# Amulet_watch_kite_d_companion.net
KiCad netlist of a schematic drawn in EAGLE
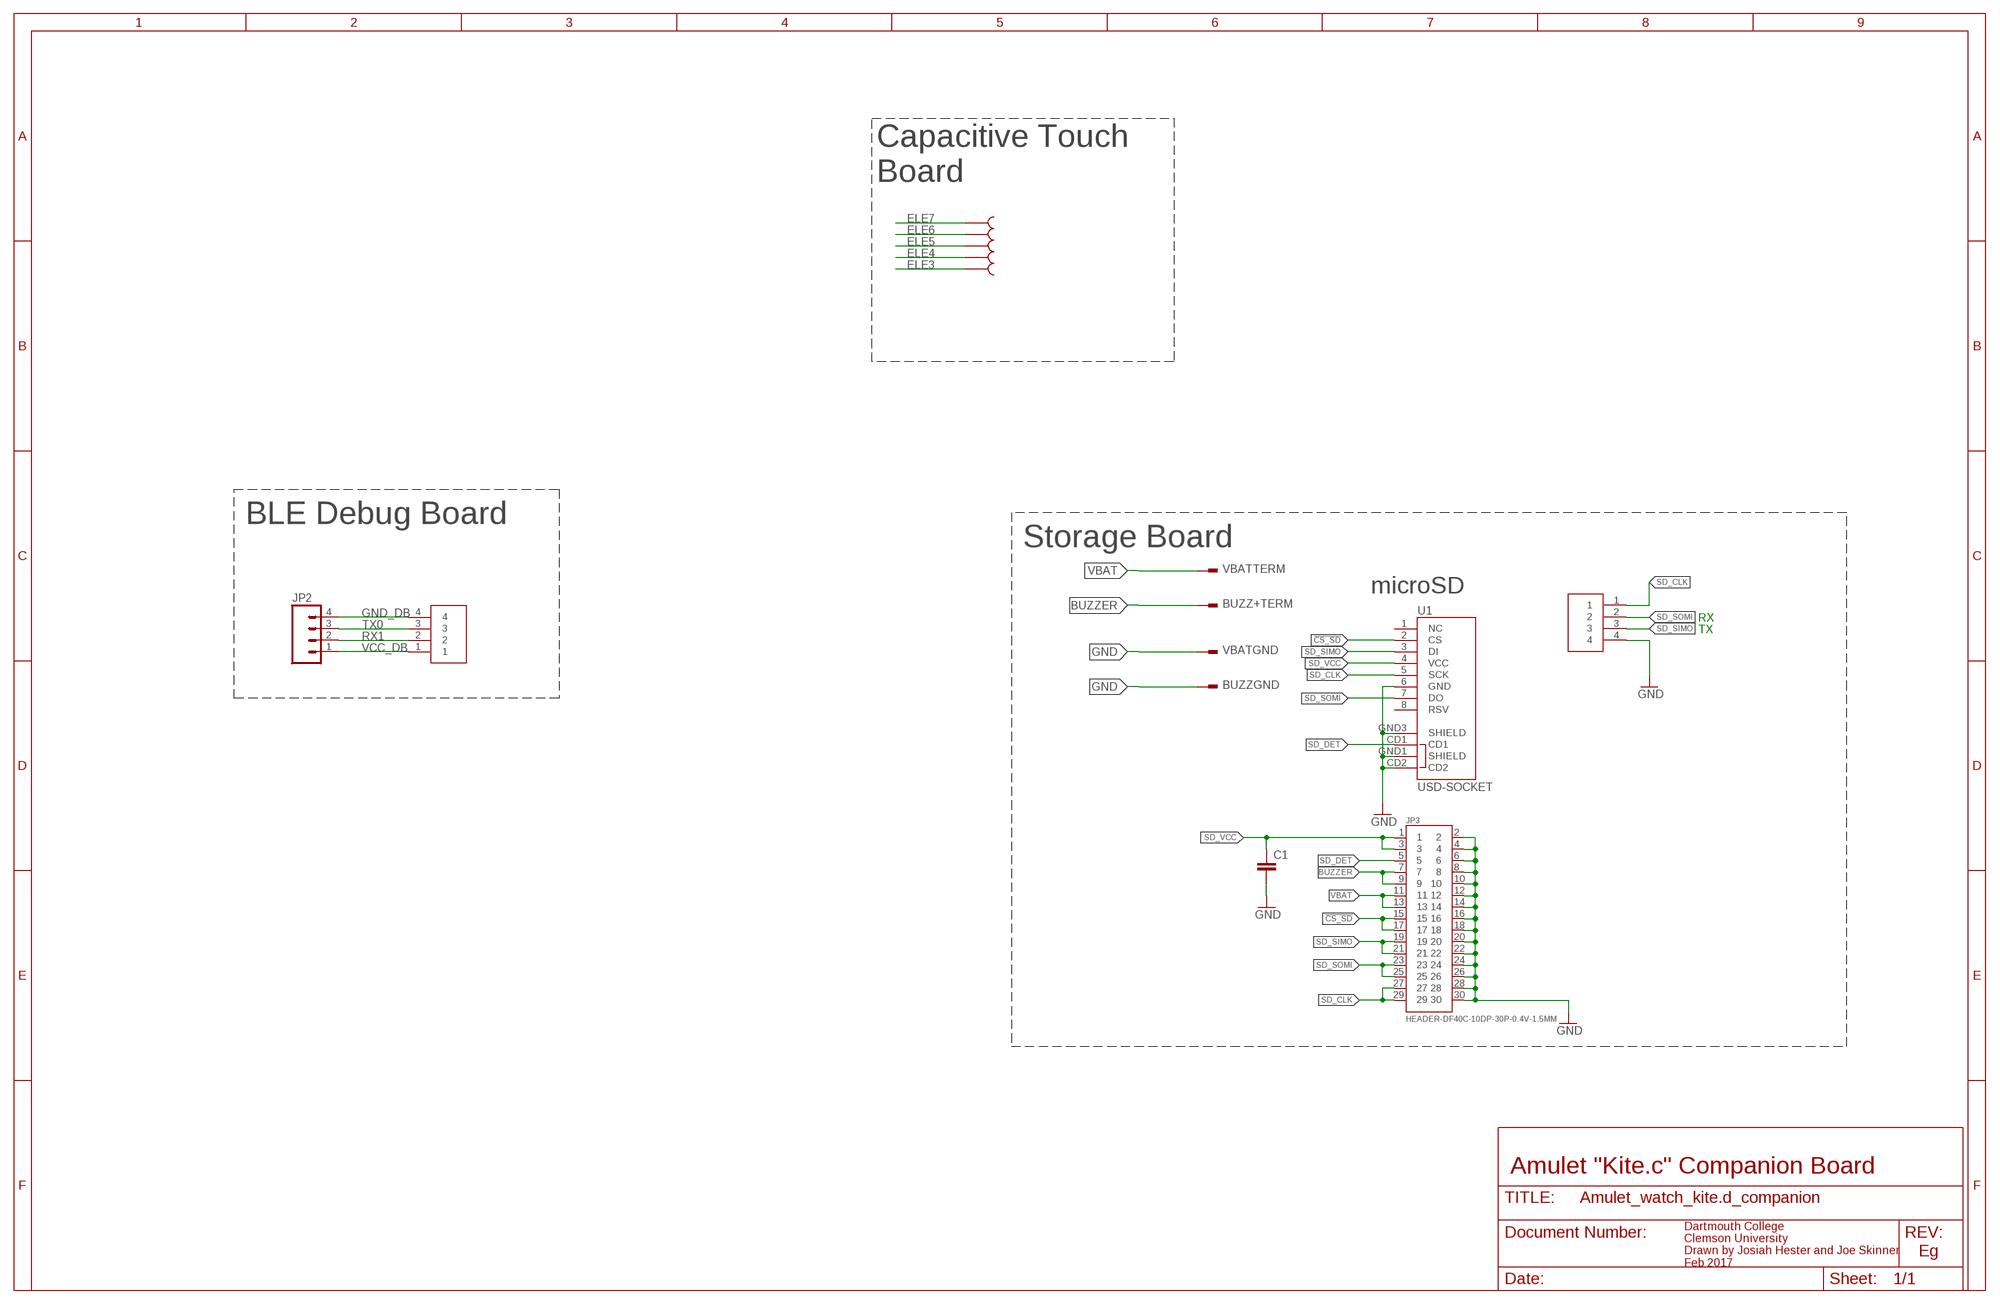
[diagram p0: schematic, sheet 1]

(export (version "E")
  (design (tool "Eeschema 10.0.6"))
  (components
    (comp (ref "BUZZ+TERM")
      (value "KITE.C.TERMINAL")
      (footprint "eagle-import:BATTERY_TERMINAL")
      (libsource (lib "eagle-import") (part "KITE.C.TERMINAL"))
    )
    (comp (ref "BUZZGND")
      (value "KITE.C.TERMINAL")
      (footprint "eagle-import:BATTERY_TERMINAL")
      (libsource (lib "eagle-import") (part "KITE.C.TERMINAL"))
    )
    (comp (ref "C1")
      (value "CAP0805")
      (footprint "eagle-import:0805")
      (libsource (lib "eagle-import") (part "CAP0805"))
    )
    (comp (ref "JP2")
      (value "M04LOCK")
      (footprint "eagle-import:1X04_LOCK")
      (libsource (lib "eagle-import") (part "M04LOCK"))
    )
    (comp (ref "JP3")
      (value "HEADER-DF40C-10DP-30P-0.4V-1.5MM")
      (footprint "eagle-import:HEADER-DF40-30")
      (fields (field (name "DIGIKEY") "H11622CT-ND "))
      (libsource (lib "eagle-import") (part "HEADER-DF40C-10DP-30P-0.4V-1.5MM"))
    )
    (comp (ref "U$1")
      (value "CTPAD")
      (footprint "eagle-import:CTPAD")
      (libsource (lib "eagle-import") (part "CTPAD"))
    )
    (comp (ref "U$2")
      (value "CTPAD")
      (footprint "eagle-import:CTPAD")
      (libsource (lib "eagle-import") (part "CTPAD"))
    )
    (comp (ref "U$3")
      (value "CTPAD")
      (footprint "eagle-import:CTPAD")
      (libsource (lib "eagle-import") (part "CTPAD"))
    )
    (comp (ref "U$4")
      (value "CTPAD")
      (footprint "eagle-import:CTPAD")
      (libsource (lib "eagle-import") (part "CTPAD"))
    )
    (comp (ref "U$5")
      (value "CTPAD")
      (footprint "eagle-import:CTPAD")
      (libsource (lib "eagle-import") (part "CTPAD"))
    )
    (comp (ref "U$11")
      (value "1.27MM-MILLMAX")
      (footprint "eagle-import:1X03-1.27MM")
      (libsource (lib "eagle-import") (part "1.27MM-MILLMAX"))
    )
    (comp (ref "U$12")
      (value "1.27MM-MILLMAX")
      (footprint "eagle-import:1X03-1.27MM")
      (libsource (lib "eagle-import") (part "1.27MM-MILLMAX"))
    )
    (comp (ref "U1")
      (value "USD-SOCKET")
      (footprint "eagle-import:MICROSD_1_1")
      (libsource (lib "eagle-import") (part "USD-SOCKET"))
    )
    (comp (ref "VBATGND")
      (value "KITE.C.TERMINAL")
      (footprint "eagle-import:BATTERY_TERMINAL")
      (libsource (lib "eagle-import") (part "KITE.C.TERMINAL"))
    )
    (comp (ref "VBATTERM")
      (value "KITE.C.TERMINAL")
      (footprint "eagle-import:BATTERY_TERMINAL")
      (libsource (lib "eagle-import") (part "KITE.C.TERMINAL"))
    )
  )
  (nets
    (net (code "1") (name "/ELE3") (class "Default")
      (node (ref "U$5") (pin "P$1") (pinfunction "P$1_P$1") (pintype "bidirectional"))
    )
    (net (code "2") (name "/ELE4") (class "Default")
      (node (ref "U$4") (pin "P$1") (pinfunction "P$1_P$1") (pintype "bidirectional"))
    )
    (net (code "3") (name "/ELE5") (class "Default")
      (node (ref "U$3") (pin "P$1") (pinfunction "P$1_P$1") (pintype "bidirectional"))
    )
    (net (code "4") (name "/ELE6") (class "Default")
      (node (ref "U$2") (pin "P$1") (pinfunction "P$1_P$1") (pintype "bidirectional"))
    )
    (net (code "5") (name "/ELE7") (class "Default")
      (node (ref "U$1") (pin "P$1") (pinfunction "P$1_P$1") (pintype "bidirectional"))
    )
    (net (code "6") (name "/GND_DB") (class "Default")
      (node (ref "JP2") (pin "4") (pinfunction "4_4") (pintype "passive"))
      (node (ref "U$12") (pin "4") (pinfunction "4_4") (pintype "bidirectional"))
    )
    (net (code "7") (name "/RX1") (class "Default")
      (node (ref "JP2") (pin "2") (pinfunction "2_2") (pintype "passive"))
      (node (ref "U$12") (pin "2") (pinfunction "2_2") (pintype "bidirectional"))
    )
    (net (code "8") (name "/TX0") (class "Default")
      (node (ref "JP2") (pin "3") (pinfunction "3_3") (pintype "passive"))
      (node (ref "U$12") (pin "3") (pinfunction "3_3") (pintype "bidirectional"))
    )
    (net (code "9") (name "/VCC_DB") (class "Default")
      (node (ref "JP2") (pin "1") (pinfunction "1_1") (pintype "passive"))
      (node (ref "U$12") (pin "1") (pinfunction "1_1") (pintype "bidirectional"))
    )
    (net (code "10") (name "/~{CS_SD}") (class "Default")
      (node (ref "JP3") (pin "15") (pinfunction "15_15") (pintype "bidirectional"))
      (node (ref "JP3") (pin "17") (pinfunction "17_17") (pintype "bidirectional"))
      (node (ref "U1") (pin "2") (pinfunction "CS_2") (pintype "bidirectional"))
    )
    (net (code "11") (name "BUZZER") (class "Default")
      (node (ref "BUZZ+TERM") (pin "P1") (pinfunction "1_P1") (pintype "passive"))
      (node (ref "JP3") (pin "7") (pinfunction "7_7") (pintype "bidirectional"))
      (node (ref "JP3") (pin "9") (pinfunction "9_9") (pintype "bidirectional"))
    )
    (net (code "12") (name "GND") (class "Default")
      (node (ref "BUZZGND") (pin "P1") (pinfunction "1_P1") (pintype "passive"))
      (node (ref "C1") (pin "2") (pinfunction "2_2") (pintype "passive"))
      (node (ref "JP3") (pin "10") (pinfunction "10_10") (pintype "bidirectional"))
      (node (ref "JP3") (pin "12") (pinfunction "12_12") (pintype "bidirectional"))
      (node (ref "JP3") (pin "14") (pinfunction "14_14") (pintype "bidirectional"))
      (node (ref "JP3") (pin "16") (pinfunction "16_16") (pintype "bidirectional"))
      (node (ref "JP3") (pin "18") (pinfunction "18_18") (pintype "bidirectional"))
      (node (ref "JP3") (pin "2") (pinfunction "2_2") (pintype "bidirectional"))
      (node (ref "JP3") (pin "20") (pinfunction "20_20") (pintype "bidirectional"))
      (node (ref "JP3") (pin "22") (pinfunction "22_22") (pintype "bidirectional"))
      (node (ref "JP3") (pin "24") (pinfunction "24_24") (pintype "bidirectional"))
      (node (ref "JP3") (pin "26") (pinfunction "26_26") (pintype "bidirectional"))
      (node (ref "JP3") (pin "28") (pinfunction "28_28") (pintype "bidirectional"))
      (node (ref "JP3") (pin "30") (pinfunction "30_30") (pintype "bidirectional"))
      (node (ref "JP3") (pin "4") (pinfunction "4_4") (pintype "bidirectional"))
      (node (ref "JP3") (pin "6") (pinfunction "6_6") (pintype "bidirectional"))
      (node (ref "JP3") (pin "8") (pinfunction "8_8") (pintype "bidirectional"))
      (node (ref "U$11") (pin "4") (pinfunction "4_4") (pintype "bidirectional"))
      (node (ref "U1") (pin "6") (pinfunction "GND_6") (pintype "bidirectional"))
      (node (ref "U1") (pin "CD2") (pinfunction "CD2_CD2") (pintype "bidirectional"))
      (node (ref "U1") (pin "GND1") (pinfunction "SHIELD_GND1") (pintype "bidirectional"))
      (node (ref "U1") (pin "GND3") (pinfunction "SHIELD_GND3") (pintype "bidirectional"))
      (node (ref "VBATGND") (pin "P1") (pinfunction "1_P1") (pintype "passive"))
    )
    (net (code "13") (name "SD_CLK") (class "Default")
      (node (ref "JP3") (pin "27") (pinfunction "27_27") (pintype "bidirectional"))
      (node (ref "JP3") (pin "29") (pinfunction "29_29") (pintype "bidirectional"))
      (node (ref "U$11") (pin "1") (pinfunction "1_1") (pintype "bidirectional"))
      (node (ref "U1") (pin "5") (pinfunction "SCK_5") (pintype "bidirectional"))
    )
    (net (code "14") (name "SD_DET") (class "Default")
      (node (ref "JP3") (pin "5") (pinfunction "5_5") (pintype "bidirectional"))
      (node (ref "U1") (pin "CD1") (pinfunction "CD1_CD1") (pintype "bidirectional"))
    )
    (net (code "15") (name "SD_SIMO") (class "Default")
      (node (ref "JP3") (pin "19") (pinfunction "19_19") (pintype "bidirectional"))
      (node (ref "JP3") (pin "21") (pinfunction "21_21") (pintype "bidirectional"))
      (node (ref "U$11") (pin "3") (pinfunction "3_3") (pintype "bidirectional"))
      (node (ref "U1") (pin "3") (pinfunction "DI_3") (pintype "bidirectional"))
    )
    (net (code "16") (name "SD_SOMI") (class "Default")
      (node (ref "JP3") (pin "23") (pinfunction "23_23") (pintype "bidirectional"))
      (node (ref "JP3") (pin "25") (pinfunction "25_25") (pintype "bidirectional"))
      (node (ref "U$11") (pin "2") (pinfunction "2_2") (pintype "bidirectional"))
      (node (ref "U1") (pin "7") (pinfunction "DO_7") (pintype "bidirectional"))
    )
    (net (code "17") (name "SD_VCC") (class "Default")
      (node (ref "C1") (pin "1") (pinfunction "1_1") (pintype "passive"))
      (node (ref "JP3") (pin "1") (pinfunction "1_1") (pintype "bidirectional"))
      (node (ref "JP3") (pin "3") (pinfunction "3_3") (pintype "bidirectional"))
      (node (ref "U1") (pin "4") (pinfunction "VCC_4") (pintype "bidirectional"))
    )
    (net (code "18") (name "VBAT") (class "Default")
      (node (ref "JP3") (pin "11") (pinfunction "11_11") (pintype "bidirectional"))
      (node (ref "JP3") (pin "13") (pinfunction "13_13") (pintype "bidirectional"))
      (node (ref "VBATTERM") (pin "P1") (pinfunction "1_P1") (pintype "passive"))
    )
    (net (code "19") (name "unconnected-(U1-NC-Pad1)") (class "Default")
      (node (ref "U1") (pin "1") (pinfunction "NC_1") (pintype "bidirectional"))
    )
    (net (code "20") (name "unconnected-(U1-RSV-Pad8)") (class "Default")
      (node (ref "U1") (pin "8") (pinfunction "RSV_8") (pintype "bidirectional"))
    )
  )
)
